# ledline.net
KiCad netlist of a schematic drawn in EAGLE
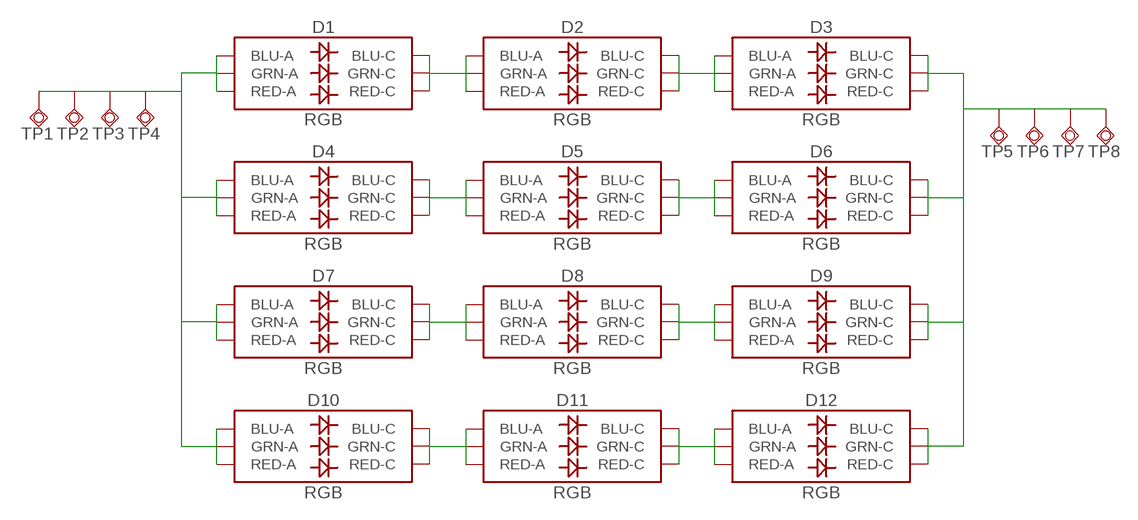
[diagram p0: schematic, sheet 1]

(export (version "E")
  (design (tool "Eeschema 10.0.6"))
  (components
    (comp (ref "D1")
      (value "RGB")
      (footprint "eagle-import:PLCC-6-LED")
      (libsource (lib "eagle-import") (part "LED-RGBPLCC-6"))
    )
    (comp (ref "D2")
      (value "RGB")
      (footprint "eagle-import:PLCC-6-LED")
      (libsource (lib "eagle-import") (part "LED-RGBPLCC-6"))
    )
    (comp (ref "D3")
      (value "RGB")
      (footprint "eagle-import:PLCC-6-LED")
      (libsource (lib "eagle-import") (part "LED-RGBPLCC-6"))
    )
    (comp (ref "D4")
      (value "RGB")
      (footprint "eagle-import:PLCC-6-LED")
      (libsource (lib "eagle-import") (part "LED-RGBPLCC-6"))
    )
    (comp (ref "D5")
      (value "RGB")
      (footprint "eagle-import:PLCC-6-LED")
      (libsource (lib "eagle-import") (part "LED-RGBPLCC-6"))
    )
    (comp (ref "D6")
      (value "RGB")
      (footprint "eagle-import:PLCC-6-LED")
      (libsource (lib "eagle-import") (part "LED-RGBPLCC-6"))
    )
    (comp (ref "D7")
      (value "RGB")
      (footprint "eagle-import:PLCC-6-LED")
      (libsource (lib "eagle-import") (part "LED-RGBPLCC-6"))
    )
    (comp (ref "D8")
      (value "RGB")
      (footprint "eagle-import:PLCC-6-LED")
      (libsource (lib "eagle-import") (part "LED-RGBPLCC-6"))
    )
    (comp (ref "D9")
      (value "RGB")
      (footprint "eagle-import:PLCC-6-LED")
      (libsource (lib "eagle-import") (part "LED-RGBPLCC-6"))
    )
    (comp (ref "D10")
      (value "RGB")
      (footprint "eagle-import:PLCC-6-LED")
      (libsource (lib "eagle-import") (part "LED-RGBPLCC-6"))
    )
    (comp (ref "D11")
      (value "RGB")
      (footprint "eagle-import:PLCC-6-LED")
      (libsource (lib "eagle-import") (part "LED-RGBPLCC-6"))
    )
    (comp (ref "D12")
      (value "RGB")
      (footprint "eagle-import:PLCC-6-LED")
      (libsource (lib "eagle-import") (part "LED-RGBPLCC-6"))
    )
    (comp (ref "TP1")
      (value "TPSQTP10SQ")
      (footprint "eagle-import:TP10SQ")
      (libsource (lib "eagle-import") (part "TPSQTP10SQ"))
    )
    (comp (ref "TP2")
      (value "TPSQTP10SQ")
      (footprint "eagle-import:TP10SQ")
      (libsource (lib "eagle-import") (part "TPSQTP10SQ"))
    )
    (comp (ref "TP3")
      (value "TPSQTP10SQ")
      (footprint "eagle-import:TP10SQ")
      (libsource (lib "eagle-import") (part "TPSQTP10SQ"))
    )
    (comp (ref "TP4")
      (value "TPSQTP10SQ")
      (footprint "eagle-import:TP10SQ")
      (libsource (lib "eagle-import") (part "TPSQTP10SQ"))
    )
    (comp (ref "TP5")
      (value "TPSQTP10SQ")
      (footprint "eagle-import:TP10SQ")
      (libsource (lib "eagle-import") (part "TPSQTP10SQ"))
    )
    (comp (ref "TP6")
      (value "TPSQTP10SQ")
      (footprint "eagle-import:TP10SQ")
      (libsource (lib "eagle-import") (part "TPSQTP10SQ"))
    )
    (comp (ref "TP7")
      (value "TPSQTP10SQ")
      (footprint "eagle-import:TP10SQ")
      (libsource (lib "eagle-import") (part "TPSQTP10SQ"))
    )
    (comp (ref "TP8")
      (value "TPSQTP10SQ")
      (footprint "eagle-import:TP10SQ")
      (libsource (lib "eagle-import") (part "TPSQTP10SQ"))
    )
  )
  (nets
    (net (code "1") (name "Net-(D1-BLU-A)") (class "Default")
      (node (ref "D1") (pin "AB") (pinfunction "BLU-A_AB") (pintype "bidirectional"))
      (node (ref "D1") (pin "AG") (pinfunction "GRN-A_AG") (pintype "bidirectional"))
      (node (ref "D1") (pin "AR") (pinfunction "RED-A_AR") (pintype "bidirectional"))
      (node (ref "D10") (pin "AB") (pinfunction "BLU-A_AB") (pintype "bidirectional"))
      (node (ref "D10") (pin "AG") (pinfunction "GRN-A_AG") (pintype "bidirectional"))
      (node (ref "D10") (pin "AR") (pinfunction "RED-A_AR") (pintype "bidirectional"))
      (node (ref "D4") (pin "AB") (pinfunction "BLU-A_AB") (pintype "bidirectional"))
      (node (ref "D4") (pin "AG") (pinfunction "GRN-A_AG") (pintype "bidirectional"))
      (node (ref "D4") (pin "AR") (pinfunction "RED-A_AR") (pintype "bidirectional"))
      (node (ref "D7") (pin "AB") (pinfunction "BLU-A_AB") (pintype "bidirectional"))
      (node (ref "D7") (pin "AG") (pinfunction "GRN-A_AG") (pintype "bidirectional"))
      (node (ref "D7") (pin "AR") (pinfunction "RED-A_AR") (pintype "bidirectional"))
      (node (ref "TP1") (pin "TP") (pinfunction "TP_TP") (pintype "input"))
      (node (ref "TP2") (pin "TP") (pinfunction "TP_TP") (pintype "input"))
      (node (ref "TP3") (pin "TP") (pinfunction "TP_TP") (pintype "input"))
      (node (ref "TP4") (pin "TP") (pinfunction "TP_TP") (pintype "input"))
    )
    (net (code "2") (name "Net-(D1-BLU-C)") (class "Default")
      (node (ref "D1") (pin "CB") (pinfunction "BLU-C_CB") (pintype "bidirectional"))
      (node (ref "D1") (pin "CG") (pinfunction "GRN-C_CG") (pintype "bidirectional"))
      (node (ref "D1") (pin "CR") (pinfunction "RED-C_CR") (pintype "bidirectional"))
      (node (ref "D2") (pin "AB") (pinfunction "BLU-A_AB") (pintype "bidirectional"))
      (node (ref "D2") (pin "AG") (pinfunction "GRN-A_AG") (pintype "bidirectional"))
      (node (ref "D2") (pin "AR") (pinfunction "RED-A_AR") (pintype "bidirectional"))
    )
    (net (code "3") (name "Net-(D2-BLU-C)") (class "Default")
      (node (ref "D2") (pin "CB") (pinfunction "BLU-C_CB") (pintype "bidirectional"))
      (node (ref "D2") (pin "CG") (pinfunction "GRN-C_CG") (pintype "bidirectional"))
      (node (ref "D2") (pin "CR") (pinfunction "RED-C_CR") (pintype "bidirectional"))
      (node (ref "D3") (pin "AB") (pinfunction "BLU-A_AB") (pintype "bidirectional"))
      (node (ref "D3") (pin "AG") (pinfunction "GRN-A_AG") (pintype "bidirectional"))
      (node (ref "D3") (pin "AR") (pinfunction "RED-A_AR") (pintype "bidirectional"))
    )
    (net (code "4") (name "Net-(D4-BLU-C)") (class "Default")
      (node (ref "D4") (pin "CB") (pinfunction "BLU-C_CB") (pintype "bidirectional"))
      (node (ref "D4") (pin "CG") (pinfunction "GRN-C_CG") (pintype "bidirectional"))
      (node (ref "D4") (pin "CR") (pinfunction "RED-C_CR") (pintype "bidirectional"))
      (node (ref "D5") (pin "AB") (pinfunction "BLU-A_AB") (pintype "bidirectional"))
      (node (ref "D5") (pin "AG") (pinfunction "GRN-A_AG") (pintype "bidirectional"))
      (node (ref "D5") (pin "AR") (pinfunction "RED-A_AR") (pintype "bidirectional"))
    )
    (net (code "5") (name "Net-(D5-BLU-C)") (class "Default")
      (node (ref "D5") (pin "CB") (pinfunction "BLU-C_CB") (pintype "bidirectional"))
      (node (ref "D5") (pin "CG") (pinfunction "GRN-C_CG") (pintype "bidirectional"))
      (node (ref "D5") (pin "CR") (pinfunction "RED-C_CR") (pintype "bidirectional"))
      (node (ref "D6") (pin "AB") (pinfunction "BLU-A_AB") (pintype "bidirectional"))
      (node (ref "D6") (pin "AG") (pinfunction "GRN-A_AG") (pintype "bidirectional"))
      (node (ref "D6") (pin "AR") (pinfunction "RED-A_AR") (pintype "bidirectional"))
    )
    (net (code "6") (name "Net-(D7-BLU-C)") (class "Default")
      (node (ref "D7") (pin "CB") (pinfunction "BLU-C_CB") (pintype "bidirectional"))
      (node (ref "D7") (pin "CG") (pinfunction "GRN-C_CG") (pintype "bidirectional"))
      (node (ref "D7") (pin "CR") (pinfunction "RED-C_CR") (pintype "bidirectional"))
      (node (ref "D8") (pin "AB") (pinfunction "BLU-A_AB") (pintype "bidirectional"))
      (node (ref "D8") (pin "AG") (pinfunction "GRN-A_AG") (pintype "bidirectional"))
      (node (ref "D8") (pin "AR") (pinfunction "RED-A_AR") (pintype "bidirectional"))
    )
    (net (code "7") (name "Net-(D8-BLU-C)") (class "Default")
      (node (ref "D8") (pin "CB") (pinfunction "BLU-C_CB") (pintype "bidirectional"))
      (node (ref "D8") (pin "CG") (pinfunction "GRN-C_CG") (pintype "bidirectional"))
      (node (ref "D8") (pin "CR") (pinfunction "RED-C_CR") (pintype "bidirectional"))
      (node (ref "D9") (pin "AB") (pinfunction "BLU-A_AB") (pintype "bidirectional"))
      (node (ref "D9") (pin "AG") (pinfunction "GRN-A_AG") (pintype "bidirectional"))
      (node (ref "D9") (pin "AR") (pinfunction "RED-A_AR") (pintype "bidirectional"))
    )
    (net (code "8") (name "Net-(D10-BLU-C)") (class "Default")
      (node (ref "D10") (pin "CB") (pinfunction "BLU-C_CB") (pintype "bidirectional"))
      (node (ref "D10") (pin "CG") (pinfunction "GRN-C_CG") (pintype "bidirectional"))
      (node (ref "D10") (pin "CR") (pinfunction "RED-C_CR") (pintype "bidirectional"))
      (node (ref "D11") (pin "AB") (pinfunction "BLU-A_AB") (pintype "bidirectional"))
      (node (ref "D11") (pin "AG") (pinfunction "GRN-A_AG") (pintype "bidirectional"))
      (node (ref "D11") (pin "AR") (pinfunction "RED-A_AR") (pintype "bidirectional"))
    )
    (net (code "9") (name "Net-(D11-BLU-C)") (class "Default")
      (node (ref "D11") (pin "CB") (pinfunction "BLU-C_CB") (pintype "bidirectional"))
      (node (ref "D11") (pin "CG") (pinfunction "GRN-C_CG") (pintype "bidirectional"))
      (node (ref "D11") (pin "CR") (pinfunction "RED-C_CR") (pintype "bidirectional"))
      (node (ref "D12") (pin "AB") (pinfunction "BLU-A_AB") (pintype "bidirectional"))
      (node (ref "D12") (pin "AG") (pinfunction "GRN-A_AG") (pintype "bidirectional"))
      (node (ref "D12") (pin "AR") (pinfunction "RED-A_AR") (pintype "bidirectional"))
    )
    (net (code "10") (name "Net-(D12-BLU-C)") (class "Default")
      (node (ref "D12") (pin "CB") (pinfunction "BLU-C_CB") (pintype "bidirectional"))
      (node (ref "D12") (pin "CG") (pinfunction "GRN-C_CG") (pintype "bidirectional"))
      (node (ref "D12") (pin "CR") (pinfunction "RED-C_CR") (pintype "bidirectional"))
      (node (ref "D3") (pin "CB") (pinfunction "BLU-C_CB") (pintype "bidirectional"))
      (node (ref "D3") (pin "CG") (pinfunction "GRN-C_CG") (pintype "bidirectional"))
      (node (ref "D3") (pin "CR") (pinfunction "RED-C_CR") (pintype "bidirectional"))
      (node (ref "D6") (pin "CB") (pinfunction "BLU-C_CB") (pintype "bidirectional"))
      (node (ref "D6") (pin "CG") (pinfunction "GRN-C_CG") (pintype "bidirectional"))
      (node (ref "D6") (pin "CR") (pinfunction "RED-C_CR") (pintype "bidirectional"))
      (node (ref "D9") (pin "CB") (pinfunction "BLU-C_CB") (pintype "bidirectional"))
      (node (ref "D9") (pin "CG") (pinfunction "GRN-C_CG") (pintype "bidirectional"))
      (node (ref "D9") (pin "CR") (pinfunction "RED-C_CR") (pintype "bidirectional"))
      (node (ref "TP5") (pin "TP") (pinfunction "TP_TP") (pintype "input"))
      (node (ref "TP6") (pin "TP") (pinfunction "TP_TP") (pintype "input"))
      (node (ref "TP7") (pin "TP") (pinfunction "TP_TP") (pintype "input"))
      (node (ref "TP8") (pin "TP") (pinfunction "TP_TP") (pintype "input"))
    )
  )
)
